# stm32f103c_marlin.net
KiCad netlist of a schematic drawn in EAGLE
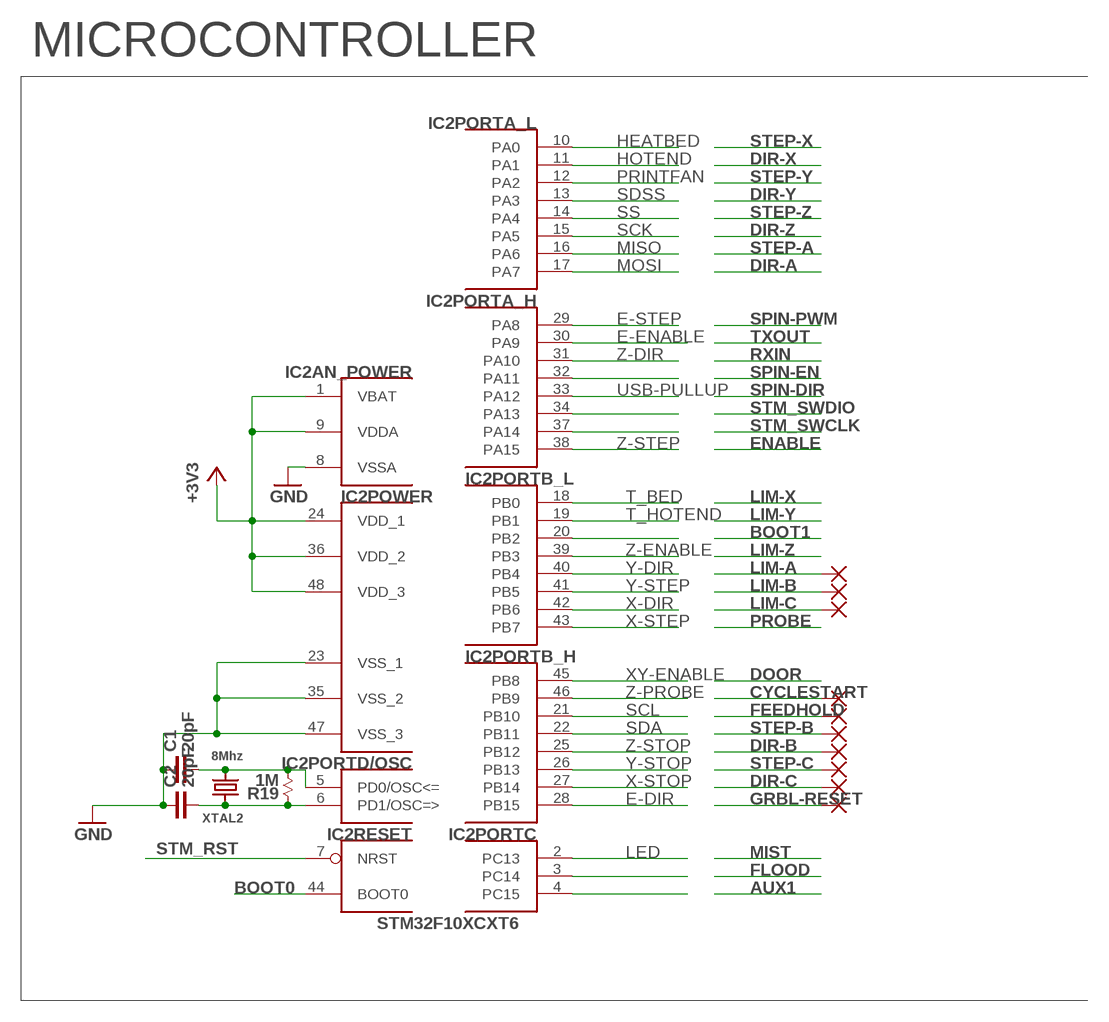
[diagram p0: schematic, sheet 1]

(export (version "E")
  (design (tool "Eeschema 10.0.6"))
  (components
    (comp (ref "C1")
      (value "20pF")
      (footprint "eagle-import:X893_0805")
      (libsource (lib "eagle-import") (part "X893_CAP-0805"))
    )
    (comp (ref "C2")
      (value "20pF")
      (footprint "eagle-import:X893_0805")
      (libsource (lib "eagle-import") (part "X893_CAP-0805"))
    )
    (comp (ref "IC2")
      (value "STM32F10XCXT6")
      (footprint "eagle-import:TQFP48")
      (libsource (lib "eagle-import") (part "STM32F10XCXT6"))
    )
    (comp (ref "PAD6")
      (value "1,6/0,8")
      (footprint "eagle-import:1,6_0,8")
      (libsource (lib "eagle-import") (part "1,6/0,8"))
    )
    (comp (ref "PAD7")
      (value "1,6/0,8")
      (footprint "eagle-import:1,6_0,8")
      (libsource (lib "eagle-import") (part "1,6/0,8"))
    )
    (comp (ref "PAD8")
      (value "1,6/0,8")
      (footprint "eagle-import:1,6_0,8")
      (libsource (lib "eagle-import") (part "1,6/0,8"))
    )
    (comp (ref "PAD9")
      (value "1,6/0,8")
      (footprint "eagle-import:1,6_0,8")
      (libsource (lib "eagle-import") (part "1,6/0,8"))
    )
    (comp (ref "PAD10")
      (value "1,6/0,8")
      (footprint "eagle-import:1,6_0,8")
      (libsource (lib "eagle-import") (part "1,6/0,8"))
    )
    (comp (ref "PAD11")
      (value "1,6/0,8")
      (footprint "eagle-import:1,6_0,8")
      (libsource (lib "eagle-import") (part "1,6/0,8"))
    )
    (comp (ref "PAD12")
      (value "1,6/0,8")
      (footprint "eagle-import:1,6_0,8")
      (libsource (lib "eagle-import") (part "1,6/0,8"))
    )
    (comp (ref "PAD13")
      (value "1,6/0,8")
      (footprint "eagle-import:1,6_0,8")
      (libsource (lib "eagle-import") (part "1,6/0,8"))
    )
    (comp (ref "PAD14")
      (value "1,6/0,8")
      (footprint "eagle-import:1,6_0,8")
      (libsource (lib "eagle-import") (part "1,6/0,8"))
    )
    (comp (ref "PAD15")
      (value "1,6/0,8")
      (footprint "eagle-import:1,6_0,8")
      (libsource (lib "eagle-import") (part "1,6/0,8"))
    )
    (comp (ref "R19")
      (value "1M")
      (footprint "eagle-import:X893_0805")
      (libsource (lib "eagle-import") (part "X893_RESISTOR-0805"))
    )
    (comp (ref "XTAL2")
      (value "8Mhz")
      (footprint "eagle-import:CRYSTAL_3.2X2.5")
      (libsource (lib "eagle-import") (part "CRYSTALTHIN"))
    )
  )
  (nets
    (net (code "1") (name "+3V3") (class "Default")
      (node (ref "IC2") (pin "1") (pinfunction "VBAT_1") (pintype "power_in"))
      (node (ref "IC2") (pin "24") (pinfunction "VDD_1_24") (pintype "power_in"))
      (node (ref "IC2") (pin "36") (pinfunction "VDD_2_36") (pintype "power_in"))
      (node (ref "IC2") (pin "48") (pinfunction "VDD_3_48") (pintype "power_in"))
      (node (ref "IC2") (pin "9") (pinfunction "VDDA_9") (pintype "power_in"))
    )
    (net (code "3") (name "/BOOT0") (class "Default")
      (node (ref "IC2") (pin "44") (pinfunction "BOOT0_44") (pintype "input"))
    )
    (net (code "5") (name "/CYCLESTART") (class "Default")
      (node (ref "PAD12") (pin "1") (pinfunction "P_1") (pintype "passive"))
    )
    (net (code "7") (name "/DIR-B") (class "Default")
      (node (ref "PAD9") (pin "1") (pinfunction "P_1") (pintype "passive"))
    )
    (net (code "8") (name "/DIR-C") (class "Default")
      (node (ref "PAD7") (pin "1") (pinfunction "P_1") (pintype "passive"))
    )
    (net (code "13") (name "/E-DIR") (class "Default")
      (node (ref "IC2") (pin "28") (pinfunction "PB15_28") (pintype "bidirectional"))
    )
    (net (code "14") (name "/E-ENABLE") (class "Default")
      (node (ref "IC2") (pin "30") (pinfunction "PA9_30") (pintype "bidirectional"))
    )
    (net (code "15") (name "/E-STEP") (class "Default")
      (node (ref "IC2") (pin "29") (pinfunction "PA8_29") (pintype "bidirectional"))
    )
    (net (code "17") (name "/FEEDHOLD") (class "Default")
      (node (ref "PAD11") (pin "1") (pinfunction "P_1") (pintype "passive"))
    )
    (net (code "19") (name "/GRBL-RESET") (class "Default")
      (node (ref "PAD6") (pin "1") (pinfunction "P_1") (pintype "passive"))
    )
    (net (code "20") (name "/HEATBED") (class "Default")
      (node (ref "IC2") (pin "10") (pinfunction "PA0_10") (pintype "bidirectional"))
    )
    (net (code "21") (name "/HOTEND") (class "Default")
      (node (ref "IC2") (pin "11") (pinfunction "PA1_11") (pintype "bidirectional"))
    )
    (net (code "22") (name "/LED") (class "Default")
      (node (ref "IC2") (pin "2") (pinfunction "PC13_2") (pintype "bidirectional"))
    )
    (net (code "23") (name "/LIM-A") (class "Default")
      (node (ref "PAD15") (pin "1") (pinfunction "P_1") (pintype "passive"))
    )
    (net (code "24") (name "/LIM-B") (class "Default")
      (node (ref "PAD14") (pin "1") (pinfunction "P_1") (pintype "passive"))
    )
    (net (code "25") (name "/LIM-C") (class "Default")
      (node (ref "PAD13") (pin "1") (pinfunction "P_1") (pintype "passive"))
    )
    (net (code "29") (name "/MISO") (class "Default")
      (node (ref "IC2") (pin "16") (pinfunction "PA6_16") (pintype "bidirectional"))
    )
    (net (code "31") (name "/MOSI") (class "Default")
      (node (ref "IC2") (pin "17") (pinfunction "PA7_17") (pintype "bidirectional"))
    )
    (net (code "32") (name "/PRINTFAN") (class "Default")
      (node (ref "IC2") (pin "12") (pinfunction "PA2_12") (pintype "bidirectional"))
    )
    (net (code "35") (name "/SCK") (class "Default")
      (node (ref "IC2") (pin "15") (pinfunction "PA5_15") (pintype "bidirectional"))
    )
    (net (code "36") (name "/SCL") (class "Default")
      (node (ref "IC2") (pin "21") (pinfunction "PB10_21") (pintype "bidirectional"))
    )
    (net (code "37") (name "/SDA") (class "Default")
      (node (ref "IC2") (pin "22") (pinfunction "PB11_22") (pintype "bidirectional"))
    )
    (net (code "38") (name "/SDSS") (class "Default")
      (node (ref "IC2") (pin "13") (pinfunction "PA3_13") (pintype "bidirectional"))
    )
    (net (code "42") (name "/SS") (class "Default")
      (node (ref "IC2") (pin "14") (pinfunction "PA4_14") (pintype "bidirectional"))
    )
    (net (code "44") (name "/STEP-B") (class "Default")
      (node (ref "PAD10") (pin "1") (pinfunction "P_1") (pintype "passive"))
    )
    (net (code "45") (name "/STEP-C") (class "Default")
      (node (ref "PAD8") (pin "1") (pinfunction "P_1") (pintype "passive"))
    )
    (net (code "49") (name "/STM_RST") (class "Default")
      (node (ref "IC2") (pin "7") (pinfunction "NRST_7") (pintype "input"))
    )
    (net (code "53") (name "/T_BED") (class "Default")
      (node (ref "IC2") (pin "18") (pinfunction "PB0_18") (pintype "bidirectional"))
    )
    (net (code "54") (name "/T_HOTEND") (class "Default")
      (node (ref "IC2") (pin "19") (pinfunction "PB1_19") (pintype "bidirectional"))
    )
    (net (code "55") (name "/USB-PULLUP") (class "Default")
      (node (ref "IC2") (pin "33") (pinfunction "PA12_33") (pintype "bidirectional"))
    )
    (net (code "56") (name "/X-DIR") (class "Default")
      (node (ref "IC2") (pin "42") (pinfunction "PB6_42") (pintype "bidirectional"))
    )
    (net (code "57") (name "/X-STEP") (class "Default")
      (node (ref "IC2") (pin "43") (pinfunction "PB7_43") (pintype "bidirectional"))
    )
    (net (code "58") (name "/X-STOP") (class "Default")
      (node (ref "IC2") (pin "27") (pinfunction "PB14_27") (pintype "bidirectional"))
    )
    (net (code "59") (name "/XY-ENABLE") (class "Default")
      (node (ref "IC2") (pin "45") (pinfunction "PB8_45") (pintype "bidirectional"))
    )
    (net (code "60") (name "/Y-DIR") (class "Default")
      (node (ref "IC2") (pin "40") (pinfunction "PB4_40") (pintype "bidirectional"))
    )
    (net (code "61") (name "/Y-STEP") (class "Default")
      (node (ref "IC2") (pin "41") (pinfunction "PB5_41") (pintype "bidirectional"))
    )
    (net (code "62") (name "/Y-STOP") (class "Default")
      (node (ref "IC2") (pin "26") (pinfunction "PB13_26") (pintype "bidirectional"))
    )
    (net (code "63") (name "/Z-DIR") (class "Default")
      (node (ref "IC2") (pin "31") (pinfunction "PA10_31") (pintype "bidirectional"))
    )
    (net (code "64") (name "/Z-ENABLE") (class "Default")
      (node (ref "IC2") (pin "39") (pinfunction "PB3_39") (pintype "bidirectional"))
    )
    (net (code "65") (name "/Z-PROBE") (class "Default")
      (node (ref "IC2") (pin "46") (pinfunction "PB9_46") (pintype "bidirectional"))
    )
    (net (code "66") (name "/Z-STEP") (class "Default")
      (node (ref "IC2") (pin "38") (pinfunction "PA15_38") (pintype "bidirectional"))
    )
    (net (code "67") (name "/Z-STOP") (class "Default")
      (node (ref "IC2") (pin "25") (pinfunction "PB12_25") (pintype "bidirectional"))
    )
    (net (code "68") (name "GND") (class "Default")
      (node (ref "C1") (pin "2") (pinfunction "2_2") (pintype "passive"))
      (node (ref "C2") (pin "2") (pinfunction "2_2") (pintype "passive"))
      (node (ref "IC2") (pin "23") (pinfunction "VSS_1_23") (pintype "power_in"))
      (node (ref "IC2") (pin "35") (pinfunction "VSS_2_35") (pintype "power_in"))
      (node (ref "IC2") (pin "47") (pinfunction "VSS_3_47") (pintype "power_in"))
      (node (ref "IC2") (pin "8") (pinfunction "VSSA_8") (pintype "power_in"))
    )
    (net (code "69") (name "Net-(IC2G-PD0{slash}OSC<=)") (class "Default")
      (node (ref "C1") (pin "1") (pinfunction "1_1") (pintype "passive"))
      (node (ref "IC2") (pin "5") (pinfunction "PD0/OSC<=_5") (pintype "bidirectional"))
      (node (ref "R19") (pin "2") (pinfunction "2_2") (pintype "passive"))
      (node (ref "XTAL2") (pin "2") (pinfunction "2_2") (pintype "passive"))
    )
    (net (code "70") (name "Net-(IC2G-PD1{slash}OSC=>)") (class "Default")
      (node (ref "C2") (pin "1") (pinfunction "1_1") (pintype "passive"))
      (node (ref "IC2") (pin "6") (pinfunction "PD1/OSC=>_6") (pintype "bidirectional"))
      (node (ref "R19") (pin "1") (pinfunction "1_1") (pintype "passive"))
      (node (ref "XTAL2") (pin "1") (pinfunction "1_1") (pintype "passive"))
    )
    (net (code "71") (name "unconnected-(IC2B-PA11-Pad32)") (class "Default")
      (node (ref "IC2") (pin "32") (pinfunction "PA11_32") (pintype "bidirectional"))
    )
    (net (code "72") (name "unconnected-(IC2B-PA13-Pad34)") (class "Default")
      (node (ref "IC2") (pin "34") (pinfunction "PA13_34") (pintype "bidirectional"))
    )
    (net (code "73") (name "unconnected-(IC2B-PA14-Pad37)") (class "Default")
      (node (ref "IC2") (pin "37") (pinfunction "PA14_37") (pintype "bidirectional"))
    )
    (net (code "74") (name "unconnected-(IC2E-PB2-Pad20)") (class "Default")
      (node (ref "IC2") (pin "20") (pinfunction "PB2_20") (pintype "bidirectional"))
    )
    (net (code "75") (name "unconnected-(IC2F-PC14-Pad3)") (class "Default")
      (node (ref "IC2") (pin "3") (pinfunction "PC14_3") (pintype "bidirectional"))
    )
    (net (code "76") (name "unconnected-(IC2F-PC15-Pad4)") (class "Default")
      (node (ref "IC2") (pin "4") (pinfunction "PC15_4") (pintype "bidirectional"))
    )
  )
)
